# MIDI-IO.net
KiCad netlist of a schematic drawn in EAGLE
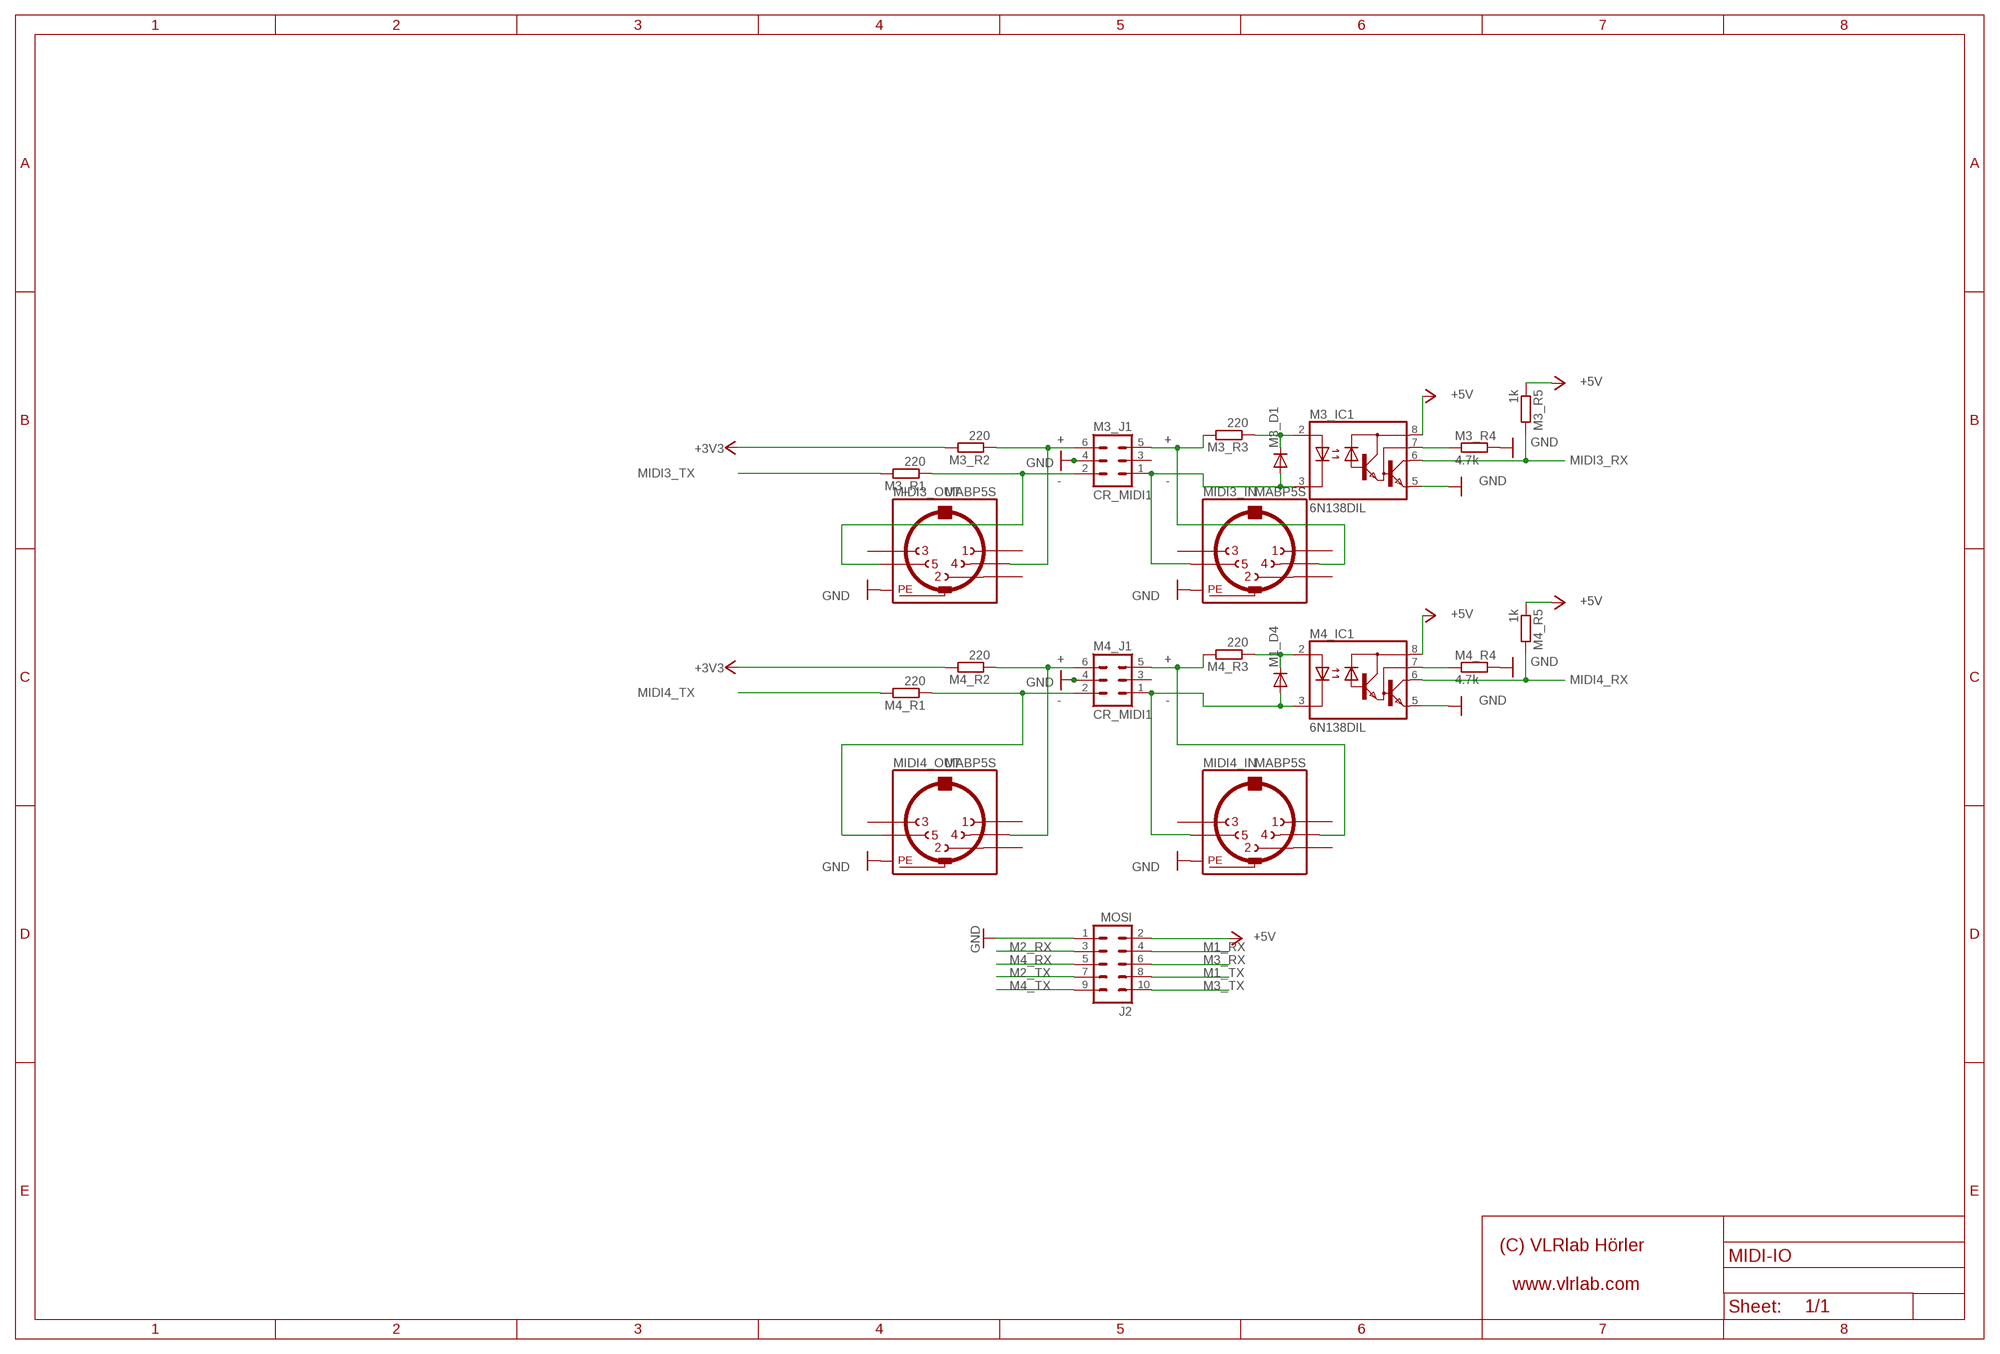
[diagram p0: schematic, sheet 1]

(export (version "E")
  (design (tool "Eeschema 10.0.6"))
  (components
    (comp (ref "J2")
      (value "MOSI")
      (footprint "eagle-import:ML10")
      (libsource (lib "eagle-import") (part "ML10"))
    )
    (comp (ref "M1_D4")
      (value "1N4148DO35-7")
      (footprint "eagle-import:DO35-7")
      (libsource (lib "eagle-import") (part "1N4148DO35-7"))
    )
    (comp (ref "M3_D1")
      (value "1N4148DO35-7")
      (footprint "eagle-import:DO35-7")
      (libsource (lib "eagle-import") (part "1N4148DO35-7"))
    )
    (comp (ref "M3_IC1")
      (value "6N138DIL")
      (footprint "eagle-import:DIL08")
      (libsource (lib "eagle-import") (part "6N138DIL"))
    )
    (comp (ref "M3_J1")
      (value "CR_MIDI1")
      (footprint "eagle-import:ML6")
      (libsource (lib "eagle-import") (part "ML6"))
    )
    (comp (ref "M3_R1")
      (value "220")
      (footprint "eagle-import:0204_7")
      (libsource (lib "eagle-import") (part "R-EU_0204/7"))
    )
    (comp (ref "M3_R2")
      (value "220")
      (footprint "eagle-import:0204_7")
      (libsource (lib "eagle-import") (part "R-EU_0204/7"))
    )
    (comp (ref "M3_R3")
      (value "220")
      (footprint "eagle-import:0204_7")
      (libsource (lib "eagle-import") (part "R-EU_0204/7"))
    )
    (comp (ref "M3_R4")
      (value "4.7k")
      (footprint "eagle-import:0204_7")
      (libsource (lib "eagle-import") (part "R-EU_0204/7"))
    )
    (comp (ref "M3_R5")
      (value "1k")
      (footprint "eagle-import:0204_7")
      (libsource (lib "eagle-import") (part "R-EU_0204/7"))
    )
    (comp (ref "M4_IC1")
      (value "6N138DIL")
      (footprint "eagle-import:DIL08")
      (libsource (lib "eagle-import") (part "6N138DIL"))
    )
    (comp (ref "M4_J1")
      (value "CR_MIDI1")
      (footprint "eagle-import:ML6")
      (libsource (lib "eagle-import") (part "ML6"))
    )
    (comp (ref "M4_R1")
      (value "220")
      (footprint "eagle-import:0204_7")
      (libsource (lib "eagle-import") (part "R-EU_0204/7"))
    )
    (comp (ref "M4_R2")
      (value "220")
      (footprint "eagle-import:0204_7")
      (libsource (lib "eagle-import") (part "R-EU_0204/7"))
    )
    (comp (ref "M4_R3")
      (value "220")
      (footprint "eagle-import:0204_7")
      (libsource (lib "eagle-import") (part "R-EU_0204/7"))
    )
    (comp (ref "M4_R4")
      (value "4.7k")
      (footprint "eagle-import:0204_7")
      (libsource (lib "eagle-import") (part "R-EU_0204/7"))
    )
    (comp (ref "M4_R5")
      (value "1k")
      (footprint "eagle-import:0204_7")
      (libsource (lib "eagle-import") (part "R-EU_0204/7"))
    )
    (comp (ref "MIDI3_IN")
      (value "MABP5S")
      (footprint "eagle-import:MABP5S")
      (libsource (lib "eagle-import") (part "MABP5S"))
    )
    (comp (ref "MIDI3_OUT")
      (value "MABP5S")
      (footprint "eagle-import:MABP5S")
      (libsource (lib "eagle-import") (part "MABP5S"))
    )
    (comp (ref "MIDI4_IN")
      (value "MABP5S")
      (footprint "eagle-import:MABP5S")
      (libsource (lib "eagle-import") (part "MABP5S"))
    )
    (comp (ref "MIDI4_OUT")
      (value "MABP5S")
      (footprint "eagle-import:MABP5S")
      (libsource (lib "eagle-import") (part "MABP5S"))
    )
  )
  (nets
    (net (code "1") (name "+3V3") (class "Default")
      (node (ref "M3_R2") (pin "2") (pinfunction "2_2") (pintype "passive"))
      (node (ref "M4_R2") (pin "2") (pinfunction "2_2") (pintype "passive"))
    )
    (net (code "2") (name "+5V") (class "Default")
      (node (ref "J2") (pin "2") (pinfunction "2_2") (pintype "passive"))
      (node (ref "M3_IC1") (pin "8") (pinfunction "VCC_8") (pintype "passive"))
      (node (ref "M3_R5") (pin "1") (pinfunction "1_1") (pintype "passive"))
      (node (ref "M4_IC1") (pin "8") (pinfunction "VCC_8") (pintype "passive"))
      (node (ref "M4_R5") (pin "1") (pinfunction "1_1") (pintype "passive"))
    )
    (net (code "3") (name "/M1_RX") (class "Default")
      (node (ref "J2") (pin "4") (pinfunction "4_4") (pintype "passive"))
    )
    (net (code "4") (name "/M1_TX") (class "Default")
      (node (ref "J2") (pin "8") (pinfunction "8_8") (pintype "passive"))
    )
    (net (code "5") (name "/M2_RX") (class "Default")
      (node (ref "J2") (pin "3") (pinfunction "3_3") (pintype "passive"))
    )
    (net (code "6") (name "/M2_TX") (class "Default")
      (node (ref "J2") (pin "7") (pinfunction "7_7") (pintype "passive"))
    )
    (net (code "7") (name "/M3_RX") (class "Default")
      (node (ref "J2") (pin "6") (pinfunction "6_6") (pintype "passive"))
    )
    (net (code "8") (name "/M3_TX") (class "Default")
      (node (ref "J2") (pin "10") (pinfunction "10_10") (pintype "passive"))
    )
    (net (code "9") (name "/M4_RX") (class "Default")
      (node (ref "J2") (pin "5") (pinfunction "5_5") (pintype "passive"))
    )
    (net (code "10") (name "/M4_TX") (class "Default")
      (node (ref "J2") (pin "9") (pinfunction "9_9") (pintype "passive"))
    )
    (net (code "11") (name "/MIDI3_RX") (class "Default")
      (node (ref "M3_IC1") (pin "6") (pinfunction "VO_6") (pintype "passive"))
      (node (ref "M3_R5") (pin "2") (pinfunction "2_2") (pintype "passive"))
    )
    (net (code "12") (name "/MIDI3_TX") (class "Default")
      (node (ref "M3_R1") (pin "2") (pinfunction "2_2") (pintype "passive"))
    )
    (net (code "13") (name "/MIDI4_RX") (class "Default")
      (node (ref "M4_IC1") (pin "6") (pinfunction "VO_6") (pintype "passive"))
      (node (ref "M4_R5") (pin "2") (pinfunction "2_2") (pintype "passive"))
    )
    (net (code "14") (name "/MIDI4_TX") (class "Default")
      (node (ref "M4_R1") (pin "2") (pinfunction "2_2") (pintype "passive"))
    )
    (net (code "15") (name "GND") (class "Default")
      (node (ref "J2") (pin "1") (pinfunction "1_1") (pintype "passive"))
      (node (ref "M3_IC1") (pin "5") (pinfunction "GND_5") (pintype "passive"))
      (node (ref "M3_J1") (pin "4") (pinfunction "4_4") (pintype "passive"))
      (node (ref "M3_R4") (pin "2") (pinfunction "2_2") (pintype "passive"))
      (node (ref "M4_IC1") (pin "5") (pinfunction "GND_5") (pintype "passive"))
      (node (ref "M4_J1") (pin "4") (pinfunction "4_4") (pintype "passive"))
      (node (ref "M4_R4") (pin "2") (pinfunction "2_2") (pintype "passive"))
      (node (ref "MIDI3_IN") (pin "PE") (pinfunction "PE_PE") (pintype "power_in"))
      (node (ref "MIDI3_IN") (pin "PE@") (pinfunction "PE_PE@") (pintype "power_in"))
      (node (ref "MIDI3_OUT") (pin "PE") (pinfunction "PE_PE") (pintype "power_in"))
      (node (ref "MIDI3_OUT") (pin "PE@") (pinfunction "PE_PE@") (pintype "power_in"))
      (node (ref "MIDI4_IN") (pin "PE") (pinfunction "PE_PE") (pintype "power_in"))
      (node (ref "MIDI4_IN") (pin "PE@") (pinfunction "PE_PE@") (pintype "power_in"))
      (node (ref "MIDI4_OUT") (pin "PE") (pinfunction "PE_PE") (pintype "power_in"))
      (node (ref "MIDI4_OUT") (pin "PE@") (pinfunction "PE_PE@") (pintype "power_in"))
    )
    (net (code "16") (name "Net-(M3_IC1-A)") (class "Default")
      (node (ref "M3_D1") (pin "C") (pinfunction "C_C") (pintype "passive"))
      (node (ref "M3_IC1") (pin "2") (pinfunction "A_2") (pintype "passive"))
      (node (ref "M3_R3") (pin "1") (pinfunction "1_1") (pintype "passive"))
    )
    (net (code "17") (name "Net-(M3_IC1-C)") (class "Default")
      (node (ref "M3_D1") (pin "A") (pinfunction "A_A") (pintype "passive"))
      (node (ref "M3_IC1") (pin "3") (pinfunction "C_3") (pintype "passive"))
      (node (ref "M3_J1") (pin "1") (pinfunction "1_1") (pintype "passive"))
      (node (ref "MIDI3_IN") (pin "5") (pinfunction "5_5") (pintype "passive"))
    )
    (net (code "18") (name "Net-(M3_IC1-VB)") (class "Default")
      (node (ref "M3_IC1") (pin "7") (pinfunction "VB_7") (pintype "passive"))
      (node (ref "M3_R4") (pin "1") (pinfunction "1_1") (pintype "passive"))
    )
    (net (code "19") (name "Net-(M3_J1-Pad2)") (class "Default")
      (node (ref "M3_J1") (pin "2") (pinfunction "2_2") (pintype "passive"))
      (node (ref "M3_R1") (pin "1") (pinfunction "1_1") (pintype "passive"))
      (node (ref "MIDI3_OUT") (pin "5") (pinfunction "5_5") (pintype "passive"))
    )
    (net (code "20") (name "Net-(M3_J1-Pad5)") (class "Default")
      (node (ref "M3_J1") (pin "5") (pinfunction "5_5") (pintype "passive"))
      (node (ref "M3_R3") (pin "2") (pinfunction "2_2") (pintype "passive"))
      (node (ref "MIDI3_IN") (pin "4") (pinfunction "4_4") (pintype "passive"))
    )
    (net (code "21") (name "Net-(M3_J1-Pad6)") (class "Default")
      (node (ref "M3_J1") (pin "6") (pinfunction "6_6") (pintype "passive"))
      (node (ref "M3_R2") (pin "1") (pinfunction "1_1") (pintype "passive"))
      (node (ref "MIDI3_OUT") (pin "4") (pinfunction "4_4") (pintype "passive"))
    )
    (net (code "22") (name "Net-(M4_IC1-A)") (class "Default")
      (node (ref "M1_D4") (pin "C") (pinfunction "C_C") (pintype "passive"))
      (node (ref "M4_IC1") (pin "2") (pinfunction "A_2") (pintype "passive"))
      (node (ref "M4_R3") (pin "1") (pinfunction "1_1") (pintype "passive"))
    )
    (net (code "23") (name "Net-(M4_IC1-C)") (class "Default")
      (node (ref "M1_D4") (pin "A") (pinfunction "A_A") (pintype "passive"))
      (node (ref "M4_IC1") (pin "3") (pinfunction "C_3") (pintype "passive"))
      (node (ref "M4_J1") (pin "1") (pinfunction "1_1") (pintype "passive"))
      (node (ref "MIDI4_IN") (pin "5") (pinfunction "5_5") (pintype "passive"))
    )
    (net (code "24") (name "Net-(M4_IC1-VB)") (class "Default")
      (node (ref "M4_IC1") (pin "7") (pinfunction "VB_7") (pintype "passive"))
      (node (ref "M4_R4") (pin "1") (pinfunction "1_1") (pintype "passive"))
    )
    (net (code "25") (name "Net-(M4_J1-Pad2)") (class "Default")
      (node (ref "M4_J1") (pin "2") (pinfunction "2_2") (pintype "passive"))
      (node (ref "M4_R1") (pin "1") (pinfunction "1_1") (pintype "passive"))
      (node (ref "MIDI4_OUT") (pin "5") (pinfunction "5_5") (pintype "passive"))
    )
    (net (code "26") (name "Net-(M4_J1-Pad5)") (class "Default")
      (node (ref "M4_J1") (pin "5") (pinfunction "5_5") (pintype "passive"))
      (node (ref "M4_R3") (pin "2") (pinfunction "2_2") (pintype "passive"))
      (node (ref "MIDI4_IN") (pin "4") (pinfunction "4_4") (pintype "passive"))
    )
    (net (code "27") (name "Net-(M4_J1-Pad6)") (class "Default")
      (node (ref "M4_J1") (pin "6") (pinfunction "6_6") (pintype "passive"))
      (node (ref "M4_R2") (pin "1") (pinfunction "1_1") (pintype "passive"))
      (node (ref "MIDI4_OUT") (pin "4") (pinfunction "4_4") (pintype "passive"))
    )
    (net (code "28") (name "unconnected-(M3_J1-Pad3)") (class "Default")
      (node (ref "M3_J1") (pin "3") (pinfunction "3_3") (pintype "passive"))
    )
    (net (code "29") (name "unconnected-(M4_J1-Pad3)") (class "Default")
      (node (ref "M4_J1") (pin "3") (pinfunction "3_3") (pintype "passive"))
    )
    (net (code "30") (name "unconnected-(MIDI3_IN-Pad1)") (class "Default")
      (node (ref "MIDI3_IN") (pin "1") (pinfunction "1_1") (pintype "passive"))
    )
    (net (code "31") (name "unconnected-(MIDI3_IN-Pad2)") (class "Default")
      (node (ref "MIDI3_IN") (pin "2") (pinfunction "2_2") (pintype "passive"))
    )
    (net (code "32") (name "unconnected-(MIDI3_IN-Pad3)") (class "Default")
      (node (ref "MIDI3_IN") (pin "3") (pinfunction "3_3") (pintype "passive"))
    )
    (net (code "33") (name "unconnected-(MIDI3_OUT-Pad1)") (class "Default")
      (node (ref "MIDI3_OUT") (pin "1") (pinfunction "1_1") (pintype "passive"))
    )
    (net (code "34") (name "unconnected-(MIDI3_OUT-Pad2)") (class "Default")
      (node (ref "MIDI3_OUT") (pin "2") (pinfunction "2_2") (pintype "passive"))
    )
    (net (code "35") (name "unconnected-(MIDI3_OUT-Pad3)") (class "Default")
      (node (ref "MIDI3_OUT") (pin "3") (pinfunction "3_3") (pintype "passive"))
    )
    (net (code "36") (name "unconnected-(MIDI4_IN-Pad1)") (class "Default")
      (node (ref "MIDI4_IN") (pin "1") (pinfunction "1_1") (pintype "passive"))
    )
    (net (code "37") (name "unconnected-(MIDI4_IN-Pad2)") (class "Default")
      (node (ref "MIDI4_IN") (pin "2") (pinfunction "2_2") (pintype "passive"))
    )
    (net (code "38") (name "unconnected-(MIDI4_IN-Pad3)") (class "Default")
      (node (ref "MIDI4_IN") (pin "3") (pinfunction "3_3") (pintype "passive"))
    )
    (net (code "39") (name "unconnected-(MIDI4_OUT-Pad1)") (class "Default")
      (node (ref "MIDI4_OUT") (pin "1") (pinfunction "1_1") (pintype "passive"))
    )
    (net (code "40") (name "unconnected-(MIDI4_OUT-Pad2)") (class "Default")
      (node (ref "MIDI4_OUT") (pin "2") (pinfunction "2_2") (pintype "passive"))
    )
    (net (code "41") (name "unconnected-(MIDI4_OUT-Pad3)") (class "Default")
      (node (ref "MIDI4_OUT") (pin "3") (pinfunction "3_3") (pintype "passive"))
    )
  )
)
